# Car_2_0.net
KiCad netlist of a schematic drawn in Altium Designer
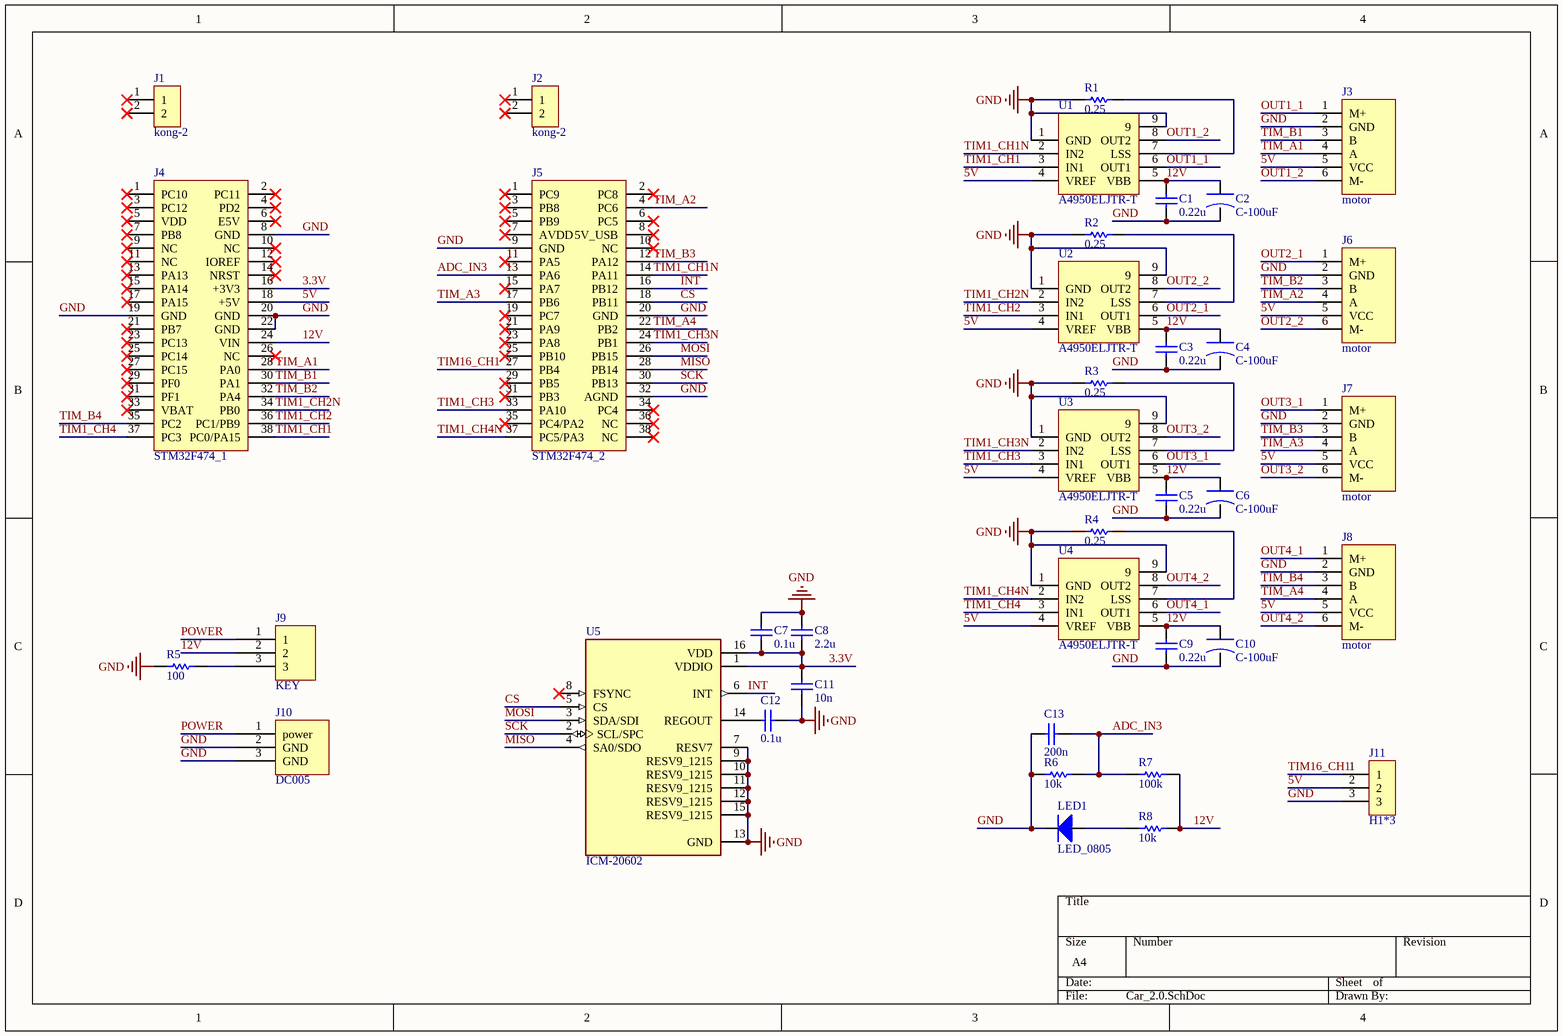
[diagram p0: Car_2.0.SchDoc]

(export (version "E")
  (design (tool "Eeschema 10.0.6"))
  (components
    (comp (ref "C1") (value "0.22u") (footprint "C_0805") (libsource (lib "Car") (part "C_0805")))
    (comp (ref "C2") (value "C-100uF") (footprint "SMD-EC-F6.3") (libsource (lib "Car") (part "C-100uF")))
    (comp (ref "C3") (value "0.22u") (footprint "C_0805") (libsource (lib "Car") (part "C_0805")))
    (comp (ref "C4") (value "C-100uF") (footprint "SMD-EC-F6.3") (libsource (lib "Car") (part "C-100uF")))
    (comp (ref "C5") (value "0.22u") (footprint "C_0805") (libsource (lib "Car") (part "C_0805")))
    (comp (ref "C6") (value "C-100uF") (footprint "SMD-EC-F6.3") (libsource (lib "Car") (part "C-100uF")))
    (comp (ref "C7") (value "0.1u") (footprint "C_0805") (libsource (lib "Car") (part "C_0805")))
    (comp (ref "C8") (value "2.2u") (footprint "C_0805") (libsource (lib "Car") (part "C_0805")))
    (comp (ref "C9") (value "0.22u") (footprint "C_0805") (libsource (lib "Car") (part "C_0805")))
    (comp (ref "C10") (value "C-100uF") (footprint "SMD-EC-F6.3") (libsource (lib "Car") (part "C-100uF")))
    (comp (ref "C11") (value "10n") (footprint "C_0805") (libsource (lib "Car") (part "C_0805")))
    (comp (ref "C12") (value "0.1u") (footprint "C_0805") (libsource (lib "Car") (part "C_0805")))
    (comp (ref "C13") (value "200n") (footprint "C_0805") (libsource (lib "GCXL_Car_1") (part "C_0805")))
    (comp (ref "J1") (value "kong-2") (footprint "HDR1X2") (libsource (lib "Car_2.0") (part "kong-2")))
    (comp (ref "J2") (value "kong-2") (footprint "HDR1X2") (libsource (lib "Car_2.0") (part "kong-2")))
    (comp (ref "J3") (value "motor") (footprint "XH2.54-6P") (libsource (lib "Car") (part "motor")))
    (comp (ref "J4")
      (value "STM32F474_1")
      (footprint "HDR2*19")
      (libsource (lib "Car_2.0") (part "STM32F474_1"))
    )
    (comp (ref "J5")
      (value "STM32F474_2")
      (footprint "HDR2*19")
      (libsource (lib "Car_2.0") (part "STM32F474_2"))
    )
    (comp (ref "J6") (value "motor") (footprint "XH2.54-6P") (libsource (lib "Car") (part "motor")))
    (comp (ref "J7") (value "motor") (footprint "XH2.54-6P") (libsource (lib "Car") (part "motor")))
    (comp (ref "J8") (value "motor") (footprint "XH2.54-6P") (libsource (lib "Car") (part "motor")))
    (comp (ref "J9") (value "KEY") (footprint "SS-12D10") (libsource (lib "Car_2.0") (part "KEY")))
    (comp (ref "J10") (value "DC005") (footprint "DC-005") (libsource (lib "Car_2.0") (part "DC005")))
    (comp (ref "J11") (value "H1*3") (footprint "HDR1X3") (libsource (lib "Car") (part "H1*3")))
    (comp (ref "LED1")
      (value "LED_0805")
      (footprint "LED0805")
      (libsource (lib "GCXL_Car_1") (part "LED_0805"))
    )
    (comp (ref "R1") (value "0.25") (footprint "R_2512") (libsource (lib "Car") (part "R-2512")))
    (comp (ref "R2") (value "0.25") (footprint "R_2512") (libsource (lib "Car") (part "R-2512")))
    (comp (ref "R3") (value "0.25") (footprint "R_2512") (libsource (lib "Car") (part "R-2512")))
    (comp (ref "R4") (value "0.25") (footprint "R_2512") (libsource (lib "Car") (part "R-2512")))
    (comp (ref "R5") (value "100") (footprint "R_0805") (libsource (lib "GCXL_Car_1") (part "R_0805")))
    (comp (ref "R6") (value "10k") (footprint "R_0805") (libsource (lib "GCXL_Car_1") (part "R_0805")))
    (comp (ref "R7") (value "100k") (footprint "R_0805") (libsource (lib "GCXL_Car_1") (part "R_0805")))
    (comp (ref "R8") (value "10k") (footprint "R_0805") (libsource (lib "GCXL_Car_1") (part "R_0805")))
    (comp (ref "U1")
      (value "A4950ELJTR-T")
      (footprint "SOIC-9N")
      (fields (field (name "MF") "RS Components") (field (name "DIGI-KEY_PART_NUMBER") "620-1400-1-ND"))
      (libsource (lib "Car_2.0") (part "A4950ELJTR-T"))
    )
    (comp (ref "U2")
      (value "A4950ELJTR-T")
      (footprint "SOIC-9N")
      (fields (field (name "MF") "RS Components") (field (name "DIGI-KEY_PART_NUMBER") "620-1400-1-ND"))
      (libsource (lib "Car_2.0") (part "A4950ELJTR-T"))
    )
    (comp (ref "U3")
      (value "A4950ELJTR-T")
      (footprint "SOIC-9N")
      (fields (field (name "MF") "RS Components") (field (name "DIGI-KEY_PART_NUMBER") "620-1400-1-ND"))
      (libsource (lib "Car_2.0") (part "A4950ELJTR-T"))
    )
    (comp (ref "U4")
      (value "A4950ELJTR-T")
      (footprint "SOIC-9N")
      (fields (field (name "MF") "RS Components") (field (name "DIGI-KEY_PART_NUMBER") "620-1400-1-ND"))
      (libsource (lib "Car_2.0") (part "A4950ELJTR-T"))
    )
    (comp (ref "U5")
      (value "ICM-20602")
      (footprint "PQFN-16N")
      (description "Accelerometer, Gyroscope, Temperature, 6 Axis Sensor IÂ²C, SPI Output")
      (fields (field (name "MF") "TDK InvenSense"))
      (libsource (lib "Car") (part "ICM-20602"))
    )
  )
  (nets
    (net (code "1") (name "/3.3V") (class "Default")
      (node (ref "C11") (pin "2") (pinfunction "2_2") (pintype "passive"))
      (node (ref "C7") (pin "2") (pinfunction "2_2") (pintype "passive"))
      (node (ref "C8") (pin "2") (pinfunction "2_2") (pintype "passive"))
      (node (ref "J4") (pin "16") (pinfunction "+3V3_16") (pintype "passive"))
      (node (ref "U5") (pin "1") (pinfunction "VDDIO_1") (pintype "power_in"))
      (node (ref "U5") (pin "16") (pinfunction "VDD_16") (pintype "power_in"))
    )
    (net (code "2") (name "/5V") (class "Default")
      (node (ref "J11") (pin "2") (pinfunction "2_2") (pintype "passive"))
      (node (ref "J3") (pin "5") (pinfunction "VCC_5") (pintype "passive"))
      (node (ref "J4") (pin "18") (pinfunction "+5V_18") (pintype "passive"))
      (node (ref "J6") (pin "5") (pinfunction "VCC_5") (pintype "passive"))
      (node (ref "J7") (pin "5") (pinfunction "VCC_5") (pintype "passive"))
      (node (ref "J8") (pin "5") (pinfunction "VCC_5") (pintype "passive"))
      (node (ref "U1") (pin "4") (pinfunction "VREF_4") (pintype "passive"))
      (node (ref "U2") (pin "4") (pinfunction "VREF_4") (pintype "passive"))
      (node (ref "U3") (pin "4") (pinfunction "VREF_4") (pintype "passive"))
      (node (ref "U4") (pin "4") (pinfunction "VREF_4") (pintype "passive"))
    )
    (net (code "3") (name "/12V") (class "Default")
      (node (ref "C1") (pin "2") (pinfunction "2_2") (pintype "passive"))
      (node (ref "C10") (pin "1") (pinfunction "1_1") (pintype "passive"))
      (node (ref "C2") (pin "1") (pinfunction "1_1") (pintype "passive"))
      (node (ref "C3") (pin "2") (pinfunction "2_2") (pintype "passive"))
      (node (ref "C4") (pin "1") (pinfunction "1_1") (pintype "passive"))
      (node (ref "C5") (pin "2") (pinfunction "2_2") (pintype "passive"))
      (node (ref "C6") (pin "1") (pinfunction "1_1") (pintype "passive"))
      (node (ref "C9") (pin "2") (pinfunction "2_2") (pintype "passive"))
      (node (ref "J4") (pin "24") (pinfunction "VIN_24") (pintype "passive"))
      (node (ref "J9") (pin "2") (pinfunction "2_2") (pintype "passive"))
      (node (ref "R7") (pin "2") (pinfunction "2_2") (pintype "passive"))
      (node (ref "R8") (pin "2") (pinfunction "2_2") (pintype "passive"))
      (node (ref "U1") (pin "5") (pinfunction "VBB_5") (pintype "passive"))
      (node (ref "U2") (pin "5") (pinfunction "VBB_5") (pintype "passive"))
      (node (ref "U3") (pin "5") (pinfunction "VBB_5") (pintype "passive"))
      (node (ref "U4") (pin "5") (pinfunction "VBB_5") (pintype "passive"))
    )
    (net (code "4") (name "/ADC_IN3") (class "Default")
      (node (ref "C13") (pin "2") (pinfunction "2_2") (pintype "passive"))
      (node (ref "J5") (pin "13") (pinfunction "PA6_13") (pintype "passive"))
      (node (ref "R6") (pin "2") (pinfunction "2_2") (pintype "passive"))
      (node (ref "R7") (pin "1") (pinfunction "1_1") (pintype "passive"))
    )
    (net (code "5") (name "/CS") (class "Default")
      (node (ref "J5") (pin "18") (pinfunction "PB11_18") (pintype "passive"))
      (node (ref "U5") (pin "5") (pinfunction "CS_5") (pintype "input"))
    )
    (net (code "6") (name "/INT") (class "Default")
      (node (ref "J5") (pin "16") (pinfunction "PB12_16") (pintype "passive"))
      (node (ref "U5") (pin "6") (pinfunction "INT_6") (pintype "output"))
    )
    (net (code "7") (name "/MISO") (class "Default")
      (node (ref "J5") (pin "28") (pinfunction "PB14_28") (pintype "passive"))
      (node (ref "U5") (pin "4") (pinfunction "SA0/SDO_4") (pintype "output"))
    )
    (net (code "8") (name "/MOSI") (class "Default")
      (node (ref "J5") (pin "26") (pinfunction "PB15_26") (pintype "passive"))
      (node (ref "U5") (pin "3") (pinfunction "SDA/SDI_3") (pintype "input"))
    )
    (net (code "9") (name "/OUT1_1") (class "Default")
      (node (ref "J3") (pin "1") (pinfunction "M+_1") (pintype "passive"))
      (node (ref "U1") (pin "6") (pinfunction "OUT1_6") (pintype "passive"))
    )
    (net (code "10") (name "/OUT1_2") (class "Default")
      (node (ref "J3") (pin "6") (pinfunction "M-_6") (pintype "passive"))
      (node (ref "U1") (pin "8") (pinfunction "OUT2_8") (pintype "passive"))
    )
    (net (code "11") (name "/OUT2_1") (class "Default")
      (node (ref "J6") (pin "1") (pinfunction "M+_1") (pintype "passive"))
      (node (ref "U2") (pin "6") (pinfunction "OUT1_6") (pintype "passive"))
    )
    (net (code "12") (name "/OUT2_2") (class "Default")
      (node (ref "J6") (pin "6") (pinfunction "M-_6") (pintype "passive"))
      (node (ref "U2") (pin "8") (pinfunction "OUT2_8") (pintype "passive"))
    )
    (net (code "13") (name "/OUT3_1") (class "Default")
      (node (ref "J7") (pin "1") (pinfunction "M+_1") (pintype "passive"))
      (node (ref "U3") (pin "6") (pinfunction "OUT1_6") (pintype "passive"))
    )
    (net (code "14") (name "/OUT3_2") (class "Default")
      (node (ref "J7") (pin "6") (pinfunction "M-_6") (pintype "passive"))
      (node (ref "U3") (pin "8") (pinfunction "OUT2_8") (pintype "passive"))
    )
    (net (code "15") (name "/OUT4_1") (class "Default")
      (node (ref "J8") (pin "1") (pinfunction "M+_1") (pintype "passive"))
      (node (ref "U4") (pin "6") (pinfunction "OUT1_6") (pintype "passive"))
    )
    (net (code "16") (name "/OUT4_2") (class "Default")
      (node (ref "J8") (pin "6") (pinfunction "M-_6") (pintype "passive"))
      (node (ref "U4") (pin "8") (pinfunction "OUT2_8") (pintype "passive"))
    )
    (net (code "17") (name "/POWER") (class "Default")
      (node (ref "J10") (pin "1") (pinfunction "power_1") (pintype "passive"))
      (node (ref "J9") (pin "1") (pinfunction "1_1") (pintype "passive"))
    )
    (net (code "18") (name "/SCK") (class "Default")
      (node (ref "J5") (pin "30") (pinfunction "PB13_30") (pintype "passive"))
      (node (ref "U5") (pin "2") (pinfunction "SCL/SPC_2") (pintype "bidirectional"))
    )
    (net (code "19") (name "/TIM1_CH1") (class "Default")
      (node (ref "J4") (pin "38") (pinfunction "PC0/PA15_38") (pintype "passive"))
      (node (ref "U1") (pin "3") (pinfunction "IN1_3") (pintype "passive"))
    )
    (net (code "20") (name "/TIM1_CH1N") (class "Default")
      (node (ref "J5") (pin "14") (pinfunction "PA11_14") (pintype "passive"))
      (node (ref "U1") (pin "2") (pinfunction "IN2_2") (pintype "passive"))
    )
    (net (code "21") (name "/TIM1_CH2") (class "Default")
      (node (ref "J4") (pin "36") (pinfunction "PC1/PB9_36") (pintype "passive"))
      (node (ref "U2") (pin "3") (pinfunction "IN1_3") (pintype "passive"))
    )
    (net (code "22") (name "/TIM1_CH2N") (class "Default")
      (node (ref "J4") (pin "34") (pinfunction "PB0_34") (pintype "passive"))
      (node (ref "U2") (pin "2") (pinfunction "IN2_2") (pintype "passive"))
    )
    (net (code "23") (name "/TIM1_CH3") (class "Default")
      (node (ref "J5") (pin "33") (pinfunction "PA10_33") (pintype "passive"))
      (node (ref "U3") (pin "3") (pinfunction "IN1_3") (pintype "passive"))
    )
    (net (code "24") (name "/TIM1_CH3N") (class "Default")
      (node (ref "J5") (pin "24") (pinfunction "PB1_24") (pintype "passive"))
      (node (ref "U3") (pin "2") (pinfunction "IN2_2") (pintype "passive"))
    )
    (net (code "25") (name "/TIM1_CH4") (class "Default")
      (node (ref "J4") (pin "37") (pinfunction "PC3_37") (pintype "passive"))
      (node (ref "U4") (pin "3") (pinfunction "IN1_3") (pintype "passive"))
    )
    (net (code "26") (name "/TIM1_CH4N") (class "Default")
      (node (ref "J5") (pin "37") (pinfunction "PC5/PA3_37") (pintype "passive"))
      (node (ref "U4") (pin "2") (pinfunction "IN2_2") (pintype "passive"))
    )
    (net (code "27") (name "/TIM16_CH1") (class "Default")
      (node (ref "J11") (pin "1") (pinfunction "1_1") (pintype "passive"))
      (node (ref "J5") (pin "27") (pinfunction "PB4_27") (pintype "passive"))
    )
    (net (code "28") (name "/TIM_A1") (class "Default")
      (node (ref "J3") (pin "4") (pinfunction "A_4") (pintype "passive"))
      (node (ref "J4") (pin "28") (pinfunction "PA0_28") (pintype "passive"))
    )
    (net (code "29") (name "/TIM_A2") (class "Default")
      (node (ref "J5") (pin "4") (pinfunction "PC6_4") (pintype "passive"))
      (node (ref "J6") (pin "4") (pinfunction "A_4") (pintype "passive"))
    )
    (net (code "30") (name "/TIM_A3") (class "Default")
      (node (ref "J5") (pin "17") (pinfunction "PB6_17") (pintype "passive"))
      (node (ref "J7") (pin "4") (pinfunction "A_4") (pintype "passive"))
    )
    (net (code "31") (name "/TIM_A4") (class "Default")
      (node (ref "J5") (pin "22") (pinfunction "PB2_22") (pintype "passive"))
      (node (ref "J8") (pin "4") (pinfunction "A_4") (pintype "passive"))
    )
    (net (code "32") (name "/TIM_B1") (class "Default")
      (node (ref "J3") (pin "3") (pinfunction "B_3") (pintype "passive"))
      (node (ref "J4") (pin "30") (pinfunction "PA1_30") (pintype "passive"))
    )
    (net (code "33") (name "/TIM_B2") (class "Default")
      (node (ref "J4") (pin "32") (pinfunction "PA4_32") (pintype "passive"))
      (node (ref "J6") (pin "3") (pinfunction "B_3") (pintype "passive"))
    )
    (net (code "34") (name "/TIM_B3") (class "Default")
      (node (ref "J5") (pin "12") (pinfunction "PA12_12") (pintype "passive"))
      (node (ref "J7") (pin "3") (pinfunction "B_3") (pintype "passive"))
    )
    (net (code "35") (name "/TIM_B4") (class "Default")
      (node (ref "J4") (pin "35") (pinfunction "PC2_35") (pintype "passive"))
      (node (ref "J8") (pin "3") (pinfunction "B_3") (pintype "passive"))
    )
    (net (code "36") (name "GND") (class "Default")
      (node (ref "C1") (pin "1") (pinfunction "1_1") (pintype "passive"))
      (node (ref "C10") (pin "2") (pinfunction "2_2") (pintype "passive"))
      (node (ref "C11") (pin "1") (pinfunction "1_1") (pintype "passive"))
      (node (ref "C12") (pin "1") (pinfunction "1_1") (pintype "passive"))
      (node (ref "C13") (pin "1") (pinfunction "1_1") (pintype "passive"))
      (node (ref "C2") (pin "2") (pinfunction "2_2") (pintype "passive"))
      (node (ref "C3") (pin "1") (pinfunction "1_1") (pintype "passive"))
      (node (ref "C4") (pin "2") (pinfunction "2_2") (pintype "passive"))
      (node (ref "C5") (pin "1") (pinfunction "1_1") (pintype "passive"))
      (node (ref "C6") (pin "2") (pinfunction "2_2") (pintype "passive"))
      (node (ref "C7") (pin "1") (pinfunction "1_1") (pintype "passive"))
      (node (ref "C8") (pin "1") (pinfunction "1_1") (pintype "passive"))
      (node (ref "C9") (pin "1") (pinfunction "1_1") (pintype "passive"))
      (node (ref "J10") (pin "2") (pinfunction "GND_2") (pintype "passive"))
      (node (ref "J10") (pin "3") (pinfunction "GND_3") (pintype "passive"))
      (node (ref "J11") (pin "3") (pinfunction "3_3") (pintype "passive"))
      (node (ref "J3") (pin "2") (pinfunction "GND_2") (pintype "passive"))
      (node (ref "J4") (pin "19") (pinfunction "GND_19") (pintype "passive"))
      (node (ref "J4") (pin "20") (pinfunction "GND_20") (pintype "passive"))
      (node (ref "J4") (pin "22") (pinfunction "GND_22") (pintype "passive"))
      (node (ref "J4") (pin "8") (pinfunction "GND_8") (pintype "passive"))
      (node (ref "J5") (pin "20") (pinfunction "GND_20") (pintype "passive"))
      (node (ref "J5") (pin "32") (pinfunction "AGND_32") (pintype "passive"))
      (node (ref "J5") (pin "9") (pinfunction "GND_9") (pintype "passive"))
      (node (ref "J6") (pin "2") (pinfunction "GND_2") (pintype "passive"))
      (node (ref "J7") (pin "2") (pinfunction "GND_2") (pintype "passive"))
      (node (ref "J8") (pin "2") (pinfunction "GND_2") (pintype "passive"))
      (node (ref "LED1") (pin "2") (pintype "passive"))
      (node (ref "R1") (pin "1") (pinfunction "1_1") (pintype "passive"))
      (node (ref "R2") (pin "1") (pinfunction "1_1") (pintype "passive"))
      (node (ref "R3") (pin "1") (pinfunction "1_1") (pintype "passive"))
      (node (ref "R4") (pin "1") (pinfunction "1_1") (pintype "passive"))
      (node (ref "R5") (pin "1") (pinfunction "1_1") (pintype "passive"))
      (node (ref "R6") (pin "1") (pinfunction "1_1") (pintype "passive"))
      (node (ref "U1") (pin "1") (pinfunction "GND_1") (pintype "passive"))
      (node (ref "U1") (pin "9") (pinfunction "9_9") (pintype "passive"))
      (node (ref "U2") (pin "1") (pinfunction "GND_1") (pintype "passive"))
      (node (ref "U2") (pin "9") (pinfunction "9_9") (pintype "passive"))
      (node (ref "U3") (pin "1") (pinfunction "GND_1") (pintype "passive"))
      (node (ref "U3") (pin "9") (pinfunction "9_9") (pintype "passive"))
      (node (ref "U4") (pin "1") (pinfunction "GND_1") (pintype "passive"))
      (node (ref "U4") (pin "9") (pinfunction "9_9") (pintype "passive"))
      (node (ref "U5") (pin "10") (pinfunction "RESV9_1215_10") (pintype "passive"))
      (node (ref "U5") (pin "11") (pinfunction "RESV9_1215_11") (pintype "passive"))
      (node (ref "U5") (pin "12") (pinfunction "RESV9_1215_12") (pintype "passive"))
      (node (ref "U5") (pin "13") (pinfunction "GND_13") (pintype "power_in"))
      (node (ref "U5") (pin "15") (pinfunction "RESV9_1215_15") (pintype "passive"))
      (node (ref "U5") (pin "7") (pinfunction "RESV7_7") (pintype "passive"))
      (node (ref "U5") (pin "9") (pinfunction "RESV9_1215_9") (pintype "passive"))
    )
    (net (code "37") (name "Net-(J9-Pad3)") (class "Default")
      (node (ref "J9") (pin "3") (pinfunction "3_3") (pintype "passive"))
      (node (ref "R5") (pin "2") (pinfunction "2_2") (pintype "passive"))
    )
    (net (code "38") (name "Net-(LED1-Pad1)") (class "Default")
      (node (ref "LED1") (pin "1") (pintype "passive"))
      (node (ref "R8") (pin "1") (pinfunction "1_1") (pintype "passive"))
    )
    (net (code "39") (name "Net-(U1-LSS)") (class "Default")
      (node (ref "R1") (pin "2") (pinfunction "2_2") (pintype "passive"))
      (node (ref "U1") (pin "7") (pinfunction "LSS_7") (pintype "passive"))
    )
    (net (code "40") (name "Net-(U2-LSS)") (class "Default")
      (node (ref "R2") (pin "2") (pinfunction "2_2") (pintype "passive"))
      (node (ref "U2") (pin "7") (pinfunction "LSS_7") (pintype "passive"))
    )
    (net (code "41") (name "Net-(U3-LSS)") (class "Default")
      (node (ref "R3") (pin "2") (pinfunction "2_2") (pintype "passive"))
      (node (ref "U3") (pin "7") (pinfunction "LSS_7") (pintype "passive"))
    )
    (net (code "42") (name "Net-(U4-LSS)") (class "Default")
      (node (ref "R4") (pin "2") (pinfunction "2_2") (pintype "passive"))
      (node (ref "U4") (pin "7") (pinfunction "LSS_7") (pintype "passive"))
    )
    (net (code "43") (name "Net-(U5-REGOUT)") (class "Default")
      (node (ref "C12") (pin "2") (pinfunction "2_2") (pintype "passive"))
      (node (ref "U5") (pin "14") (pinfunction "REGOUT_14") (pintype "passive"))
    )
    (net (code "44") (name "unconnected-(J1-Pad1)") (class "Default")
      (node (ref "J1") (pin "1") (pinfunction "1_1") (pintype "passive+no_connect"))
    )
    (net (code "45") (name "unconnected-(J1-Pad2)") (class "Default")
      (node (ref "J1") (pin "2") (pinfunction "2_2") (pintype "passive+no_connect"))
    )
    (net (code "46") (name "unconnected-(J2-Pad1)") (class "Default")
      (node (ref "J2") (pin "1") (pinfunction "1_1") (pintype "passive+no_connect"))
    )
    (net (code "47") (name "unconnected-(J2-Pad2)") (class "Default")
      (node (ref "J2") (pin "2") (pinfunction "2_2") (pintype "passive+no_connect"))
    )
    (net (code "48") (name "unconnected-(J4-E5V-Pad6)") (class "Default")
      (node (ref "J4") (pin "6") (pinfunction "E5V_6") (pintype "passive+no_connect"))
    )
    (net (code "49") (name "unconnected-(J4-IOREF-Pad12)") (class "Default")
      (node (ref "J4") (pin "12") (pinfunction "IOREF_12") (pintype "passive+no_connect"))
    )
    (net (code "50") (name "unconnected-(J4-NC-Pad9)") (class "Default")
      (node (ref "J4") (pin "9") (pinfunction "NC_9") (pintype "passive+no_connect"))
    )
    (net (code "51") (name "unconnected-(J4-NC-Pad10)") (class "Default")
      (node (ref "J4") (pin "10") (pinfunction "NC_10") (pintype "passive+no_connect"))
    )
    (net (code "52") (name "unconnected-(J4-NC-Pad11)") (class "Default")
      (node (ref "J4") (pin "11") (pinfunction "NC_11") (pintype "passive+no_connect"))
    )
    (net (code "53") (name "unconnected-(J4-NC-Pad26)") (class "Default")
      (node (ref "J4") (pin "26") (pinfunction "NC_26") (pintype "passive+no_connect"))
    )
    (net (code "54") (name "unconnected-(J4-NRST-Pad14)") (class "Default")
      (node (ref "J4") (pin "14") (pinfunction "NRST_14") (pintype "passive+no_connect"))
    )
    (net (code "55") (name "unconnected-(J4-PA13-Pad13)") (class "Default")
      (node (ref "J4") (pin "13") (pinfunction "PA13_13") (pintype "passive+no_connect"))
    )
    (net (code "56") (name "unconnected-(J4-PA14-Pad15)") (class "Default")
      (node (ref "J4") (pin "15") (pinfunction "PA14_15") (pintype "passive+no_connect"))
    )
    (net (code "57") (name "unconnected-(J4-PA15-Pad17)") (class "Default")
      (node (ref "J4") (pin "17") (pinfunction "PA15_17") (pintype "passive+no_connect"))
    )
    (net (code "58") (name "unconnected-(J4-PB7-Pad21)") (class "Default")
      (node (ref "J4") (pin "21") (pinfunction "PB7_21") (pintype "passive+no_connect"))
    )
    (net (code "59") (name "unconnected-(J4-PB8-Pad7)") (class "Default")
      (node (ref "J4") (pin "7") (pinfunction "PB8_7") (pintype "passive+no_connect"))
    )
    (net (code "60") (name "unconnected-(J4-PC10-Pad1)") (class "Default")
      (node (ref "J4") (pin "1") (pinfunction "PC10_1") (pintype "passive+no_connect"))
    )
    (net (code "61") (name "unconnected-(J4-PC11-Pad2)") (class "Default")
      (node (ref "J4") (pin "2") (pinfunction "PC11_2") (pintype "passive+no_connect"))
    )
    (net (code "62") (name "unconnected-(J4-PC12-Pad3)") (class "Default")
      (node (ref "J4") (pin "3") (pinfunction "PC12_3") (pintype "passive+no_connect"))
    )
    (net (code "63") (name "unconnected-(J4-PC13-Pad23)") (class "Default")
      (node (ref "J4") (pin "23") (pinfunction "PC13_23") (pintype "passive+no_connect"))
    )
    (net (code "64") (name "unconnected-(J4-PC14-Pad25)") (class "Default")
      (node (ref "J4") (pin "25") (pinfunction "PC14_25") (pintype "passive+no_connect"))
    )
    (net (code "65") (name "unconnected-(J4-PC15-Pad27)") (class "Default")
      (node (ref "J4") (pin "27") (pinfunction "PC15_27") (pintype "passive+no_connect"))
    )
    (net (code "66") (name "unconnected-(J4-PD2-Pad4)") (class "Default")
      (node (ref "J4") (pin "4") (pinfunction "PD2_4") (pintype "passive+no_connect"))
    )
    (net (code "67") (name "unconnected-(J4-PF0-Pad29)") (class "Default")
      (node (ref "J4") (pin "29") (pinfunction "PF0_29") (pintype "passive+no_connect"))
    )
    (net (code "68") (name "unconnected-(J4-PF1-Pad31)") (class "Default")
      (node (ref "J4") (pin "31") (pinfunction "PF1_31") (pintype "passive+no_connect"))
    )
    (net (code "69") (name "unconnected-(J4-VBAT-Pad33)") (class "Default")
      (node (ref "J4") (pin "33") (pinfunction "VBAT_33") (pintype "passive+no_connect"))
    )
    (net (code "70") (name "unconnected-(J4-VDD-Pad5)") (class "Default")
      (node (ref "J4") (pin "5") (pinfunction "VDD_5") (pintype "passive+no_connect"))
    )
    (net (code "71") (name "unconnected-(J5-5V_USB-Pad8)") (class "Default")
      (node (ref "J5") (pin "8") (pinfunction "5V_USB_8") (pintype "passive+no_connect"))
    )
    (net (code "72") (name "unconnected-(J5-AVDD-Pad7)") (class "Default")
      (node (ref "J5") (pin "7") (pinfunction "AVDD_7") (pintype "passive+no_connect"))
    )
    (net (code "73") (name "unconnected-(J5-NC-Pad10)") (class "Default")
      (node (ref "J5") (pin "10") (pinfunction "NC_10") (pintype "passive+no_connect"))
    )
    (net (code "74") (name "unconnected-(J5-NC-Pad36)") (class "Default")
      (node (ref "J5") (pin "36") (pinfunction "NC_36") (pintype "passive+no_connect"))
    )
    (net (code "75") (name "unconnected-(J5-NC-Pad38)") (class "Default")
      (node (ref "J5") (pin "38") (pinfunction "NC_38") (pintype "passive+no_connect"))
    )
    (net (code "76") (name "unconnected-(J5-PA5-Pad11)") (class "Default")
      (node (ref "J5") (pin "11") (pinfunction "PA5_11") (pintype "passive+no_connect"))
    )
    (net (code "77") (name "unconnected-(J5-PA7-Pad15)") (class "Default")
      (node (ref "J5") (pin "15") (pinfunction "PA7_15") (pintype "passive+no_connect"))
    )
    (net (code "78") (name "unconnected-(J5-PA8-Pad23)") (class "Default")
      (node (ref "J5") (pin "23") (pinfunction "PA8_23") (pintype "passive+no_connect"))
    )
    (net (code "79") (name "unconnected-(J5-PA9-Pad21)") (class "Default")
      (node (ref "J5") (pin "21") (pinfunction "PA9_21") (pintype "passive+no_connect"))
    )
    (net (code "80") (name "unconnected-(J5-PB3-Pad31)") (class "Default")
      (node (ref "J5") (pin "31") (pinfunction "PB3_31") (pintype "passive+no_connect"))
    )
    (net (code "81") (name "unconnected-(J5-PB5-Pad29)") (class "Default")
      (node (ref "J5") (pin "29") (pinfunction "PB5_29") (pintype "passive+no_connect"))
    )
    (net (code "82") (name "unconnected-(J5-PB8-Pad3)") (class "Default")
      (node (ref "J5") (pin "3") (pinfunction "PB8_3") (pintype "passive+no_connect"))
    )
    (net (code "83") (name "unconnected-(J5-PB9-Pad5)") (class "Default")
      (node (ref "J5") (pin "5") (pinfunction "PB9_5") (pintype "passive+no_connect"))
    )
    (net (code "84") (name "unconnected-(J5-PB10-Pad25)") (class "Default")
      (node (ref "J5") (pin "25") (pinfunction "PB10_25") (pintype "passive+no_connect"))
    )
    (net (code "85") (name "unconnected-(J5-PC4-Pad34)") (class "Default")
      (node (ref "J5") (pin "34") (pinfunction "PC4_34") (pintype "passive+no_connect"))
    )
    (net (code "86") (name "unconnected-(J5-PC4{slash}PA2-Pad35)") (class "Default")
      (node (ref "J5") (pin "35") (pinfunction "PC4/PA2_35") (pintype "passive+no_connect"))
    )
    (net (code "87") (name "unconnected-(J5-PC5-Pad6)") (class "Default")
      (node (ref "J5") (pin "6") (pinfunction "PC5_6") (pintype "passive+no_connect"))
    )
    (net (code "88") (name "unconnected-(J5-PC7-Pad19)") (class "Default")
      (node (ref "J5") (pin "19") (pinfunction "PC7_19") (pintype "passive+no_connect"))
    )
    (net (code "89") (name "unconnected-(J5-PC8-Pad2)") (class "Default")
      (node (ref "J5") (pin "2") (pinfunction "PC8_2") (pintype "passive+no_connect"))
    )
    (net (code "90") (name "unconnected-(J5-PC9-Pad1)") (class "Default")
      (node (ref "J5") (pin "1") (pinfunction "PC9_1") (pintype "passive+no_connect"))
    )
    (net (code "91") (name "unconnected-(U5-FSYNC-Pad8)") (class "Default")
      (node (ref "U5") (pin "8") (pinfunction "FSYNC_8") (pintype "input+no_connect"))
    )
  )
)
